# 03_iMX_8X_PMIC.net
KiCad netlist of a schematic drawn in Altium Designer
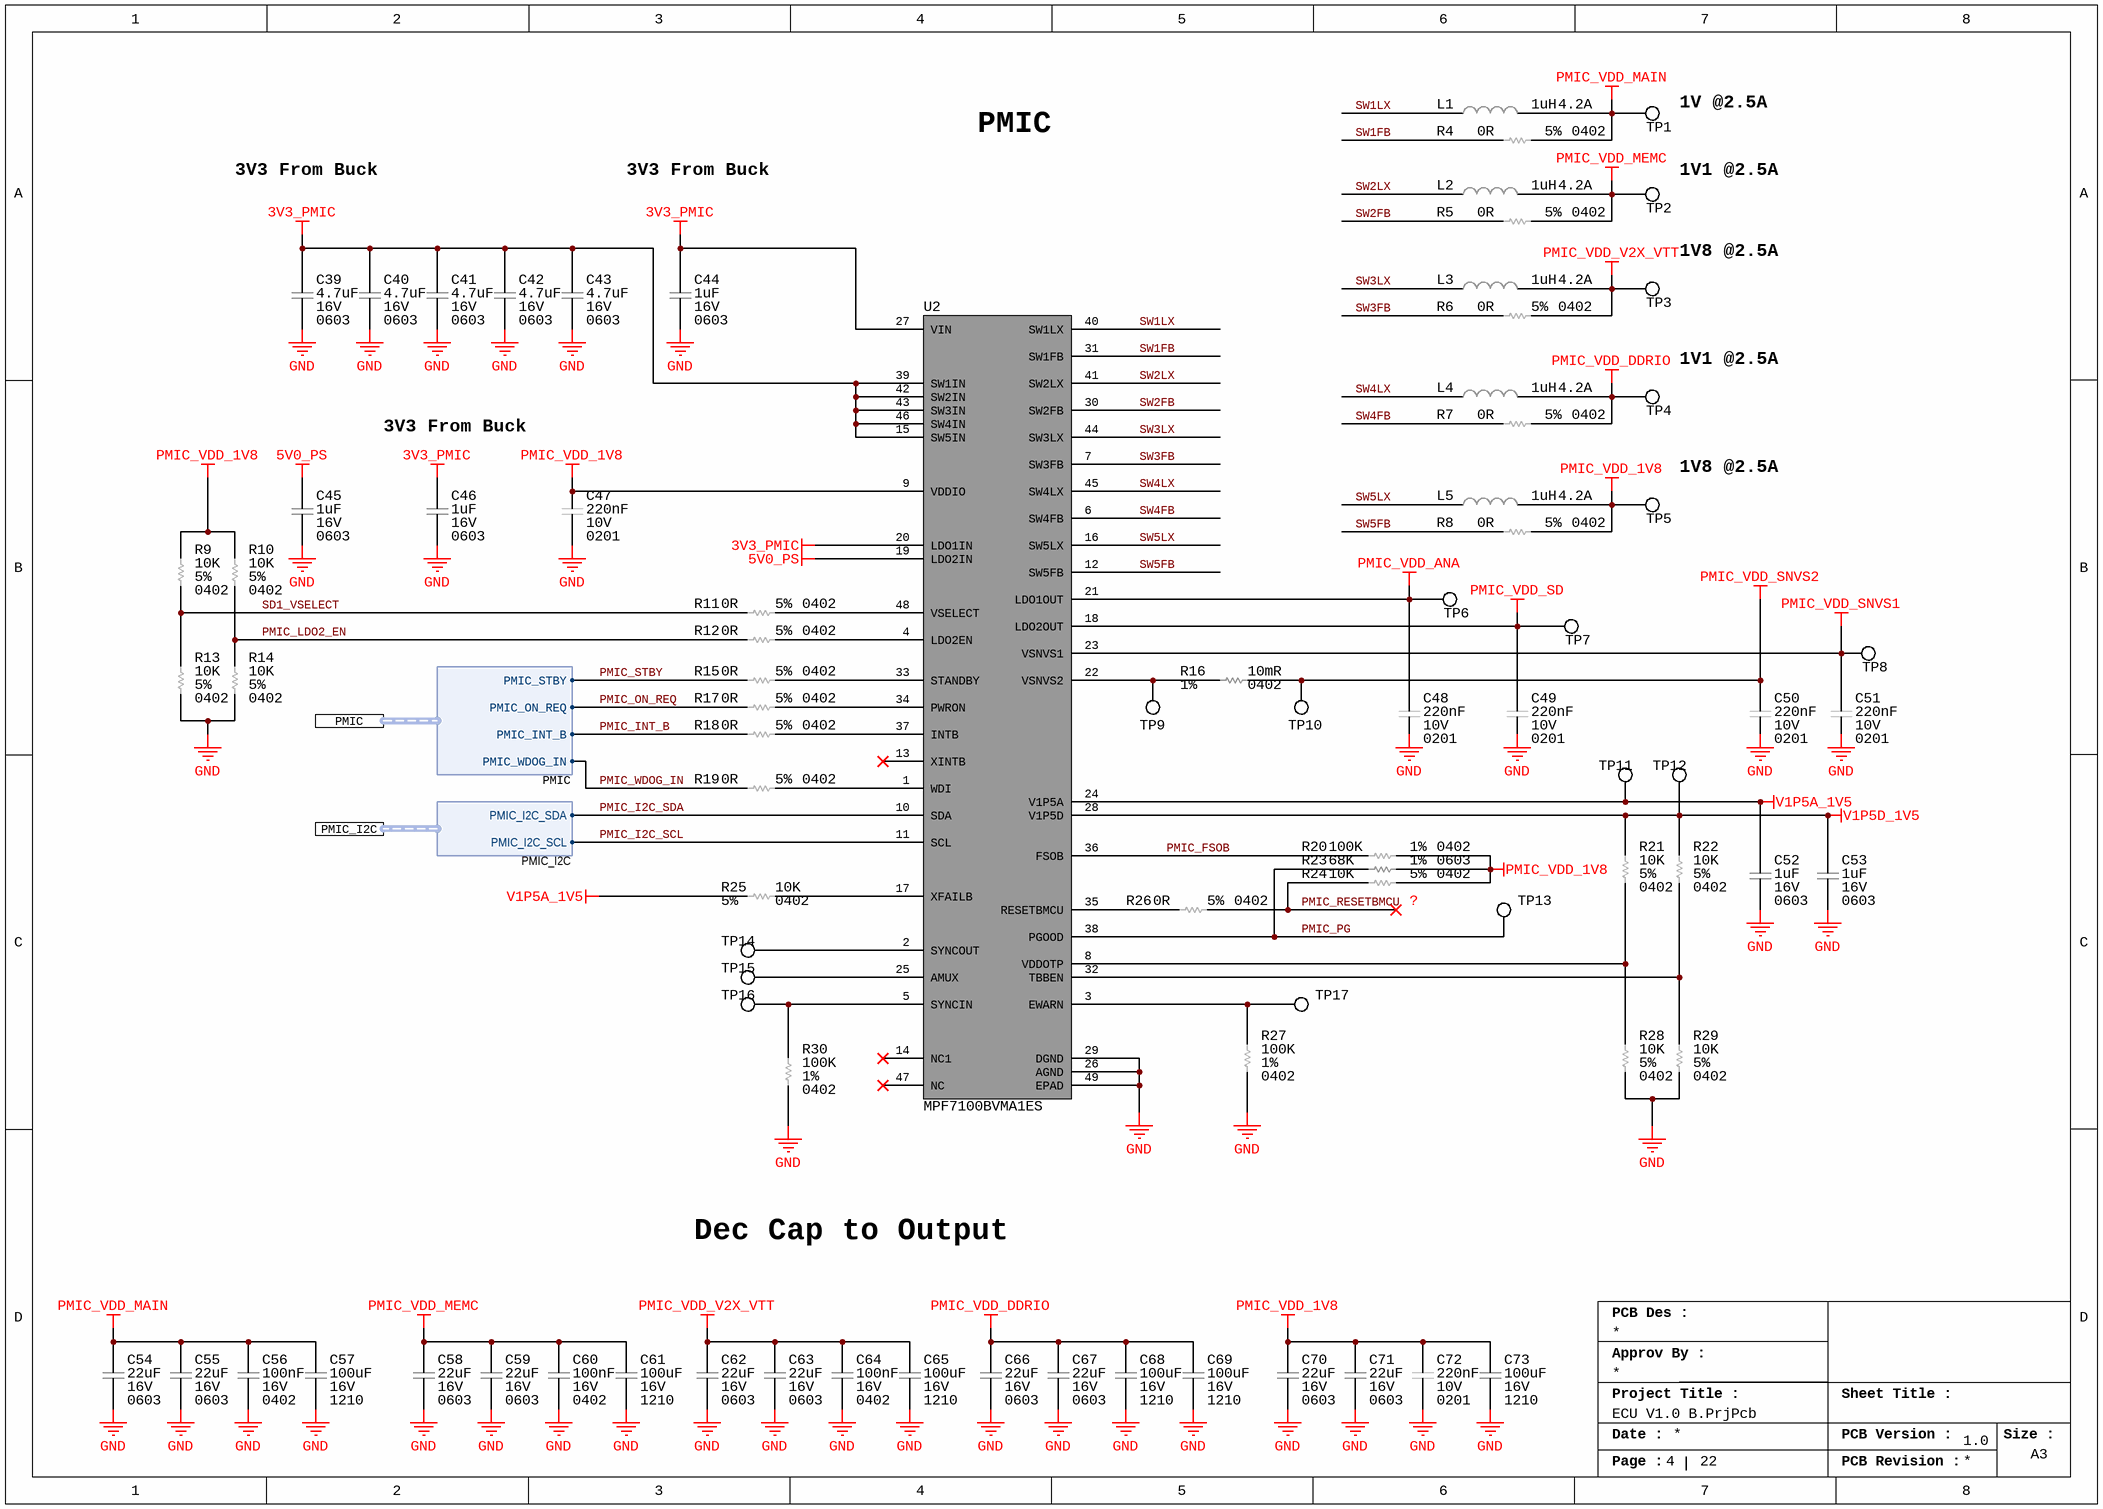
[diagram p0: 03_iMX 8X_PMIC.SchDoc]

(export (version "E")
  (design (tool "Eeschema 10.0.6"))
  (components
    (comp (ref "C39")
      (value "CL10A475KO8NNNC")
      (footprint "CAP_0603_CAPC1608X08N")
      (description "CAP CER 4.7UF 16V X5R 0603")
      (fields
        (field (name "MANUFACTURER") "Samsung")
        (field (name "TOLERANCE") "10%")
        (field (name "VOLTAGE") "16V")
        (field (name "CAPACITANCE") "4.7uF")
        (field (name "CASE/PACKAGE") "0603")
      )
      (libsource (lib "Electronic Devices_LIB") (part "CAP_4.7UF_16V_X5R_0603"))
    )
    (comp (ref "C40")
      (value "CL10A475KO8NNNC")
      (footprint "CAP_0603_CAPC1608X08N")
      (description "CAP CER 4.7UF 16V X5R 0603")
      (fields
        (field (name "MANUFACTURER") "Samsung")
        (field (name "TOLERANCE") "10%")
        (field (name "VOLTAGE") "16V")
        (field (name "CAPACITANCE") "4.7uF")
        (field (name "CASE/PACKAGE") "0603")
      )
      (libsource (lib "Electronic Devices_LIB") (part "CAP_4.7UF_16V_X5R_0603"))
    )
    (comp (ref "C41")
      (value "CL10A475KO8NNNC")
      (footprint "CAP_0603_CAPC1608X08N")
      (description "CAP CER 4.7UF 16V X5R 0603")
      (fields
        (field (name "MANUFACTURER") "Samsung")
        (field (name "TOLERANCE") "10%")
        (field (name "VOLTAGE") "16V")
        (field (name "CAPACITANCE") "4.7uF")
        (field (name "CASE/PACKAGE") "0603")
      )
      (libsource (lib "Electronic Devices_LIB") (part "CAP_4.7UF_16V_X5R_0603"))
    )
    (comp (ref "C42")
      (value "CL10A475KO8NNNC")
      (footprint "CAP_0603_CAPC1608X08N")
      (description "CAP CER 4.7UF 16V X5R 0603")
      (fields
        (field (name "MANUFACTURER") "Samsung")
        (field (name "TOLERANCE") "10%")
        (field (name "VOLTAGE") "16V")
        (field (name "CAPACITANCE") "4.7uF")
        (field (name "CASE/PACKAGE") "0603")
      )
      (libsource (lib "Electronic Devices_LIB") (part "CAP_4.7UF_16V_X5R_0603"))
    )
    (comp (ref "C43")
      (value "CL10A475KO8NNNC")
      (footprint "CAP_0603_CAPC1608X08N")
      (description "CAP CER 4.7UF 16V X5R 0603")
      (fields
        (field (name "MANUFACTURER") "Samsung")
        (field (name "TOLERANCE") "10%")
        (field (name "VOLTAGE") "16V")
        (field (name "CAPACITANCE") "4.7uF")
        (field (name "CASE/PACKAGE") "0603")
      )
      (libsource (lib "Electronic Devices_LIB") (part "CAP_4.7UF_16V_X5R_0603"))
    )
    (comp (ref "C44")
      (value "CL10A105KO8NNNC")
      (footprint "CAP_0603_CAPC1608X08N")
      (description "CAP CER 1UF 16V X5R 0603")
      (fields
        (field (name "MANUFACTURER") "Samsung")
        (field (name "TOLERANCE") "10%")
        (field (name "VOLTAGE RATING") "16V")
        (field (name "CAPACITANCE") "1uF")
        (field (name "CASE/PACKAGE") "0603")
      )
      (libsource (lib "Electronic Devices_LIB") (part "CAP_1UF_16V_X5R_0603"))
    )
    (comp (ref "C45")
      (value "CL10A105KO8NNNC")
      (footprint "CAP_0603_CAPC1608X08N")
      (description "CAP CER 1UF 16V X5R 0603")
      (fields
        (field (name "MANUFACTURER") "Samsung")
        (field (name "TOLERANCE") "10%")
        (field (name "VOLTAGE RATING") "16V")
        (field (name "CAPACITANCE") "1uF")
        (field (name "CASE/PACKAGE") "0603")
      )
      (libsource (lib "Electronic Devices_LIB") (part "CAP_1UF_16V_X5R_0603"))
    )
    (comp (ref "C46")
      (value "CL10A105KO8NNNC")
      (footprint "CAP_0603_CAPC1608X08N")
      (description "CAP CER 1UF 16V X5R 0603")
      (fields
        (field (name "MANUFACTURER") "Samsung")
        (field (name "TOLERANCE") "10%")
        (field (name "VOLTAGE RATING") "16V")
        (field (name "CAPACITANCE") "1uF")
        (field (name "CASE/PACKAGE") "0603")
      )
      (libsource (lib "Electronic Devices_LIB") (part "CAP_1UF_16V_X5R_0603"))
    )
    (comp (ref "C47")
      (value "LMK063BJ224MP-F")
      (footprint "CAP_0201_CAPC0603X03N")
      (description "Multilayer Ceramic Capacitors (High dielectric type), 10V, 0.22 uF, ± 20 %, 0201, X5R, RoHS")
      (fields
        (field (name "MANUFACTURER") "Taiyo Yuden")
        (field (name "TOLERANCE") "20%")
        (field (name "VOLTAGE RATING (DC)") "10V")
        (field (name "CAPACITANCE") "220nF")
        (field (name "CASE/PACKAGE") "0201")
      )
      (libsource (lib "Electronic Devices_LIB") (part "CAP_0.22UF_10V_X5R_0201"))
    )
    (comp (ref "C48")
      (value "LMK063BJ224MP-F")
      (footprint "CAP_0201_CAPC0603X03N")
      (description "Multilayer Ceramic Capacitors (High dielectric type), 10V, 0.22 uF, ± 20 %, 0201, X5R, RoHS")
      (fields
        (field (name "MANUFACTURER") "Taiyo Yuden")
        (field (name "TOLERANCE") "20%")
        (field (name "VOLTAGE RATING (DC)") "10V")
        (field (name "CAPACITANCE") "220nF")
        (field (name "CASE/PACKAGE") "0201")
      )
      (libsource (lib "Electronic Devices_LIB") (part "CAP_0.22UF_10V_X5R_0201"))
    )
    (comp (ref "C49")
      (value "LMK063BJ224MP-F")
      (footprint "CAP_0201_CAPC0603X03N")
      (description "Multilayer Ceramic Capacitors (High dielectric type), 10V, 0.22 uF, ± 20 %, 0201, X5R, RoHS")
      (fields
        (field (name "MANUFACTURER") "Taiyo Yuden")
        (field (name "TOLERANCE") "20%")
        (field (name "VOLTAGE RATING (DC)") "10V")
        (field (name "CAPACITANCE") "220nF")
        (field (name "CASE/PACKAGE") "0201")
      )
      (libsource (lib "Electronic Devices_LIB") (part "CAP_0.22UF_10V_X5R_0201"))
    )
    (comp (ref "C50")
      (value "LMK063BJ224MP-F")
      (footprint "CAP_0201_CAPC0603X03N")
      (description "Multilayer Ceramic Capacitors (High dielectric type), 10V, 0.22 uF, ± 20 %, 0201, X5R, RoHS")
      (fields
        (field (name "MANUFACTURER") "Taiyo Yuden")
        (field (name "TOLERANCE") "20%")
        (field (name "VOLTAGE RATING (DC)") "10V")
        (field (name "CAPACITANCE") "220nF")
        (field (name "CASE/PACKAGE") "0201")
      )
      (libsource (lib "Electronic Devices_LIB") (part "CAP_0.22UF_10V_X5R_0201"))
    )
    (comp (ref "C51")
      (value "LMK063BJ224MP-F")
      (footprint "CAP_0201_CAPC0603X03N")
      (description "Multilayer Ceramic Capacitors (High dielectric type), 10V, 0.22 uF, ± 20 %, 0201, X5R, RoHS")
      (fields
        (field (name "MANUFACTURER") "Taiyo Yuden")
        (field (name "TOLERANCE") "20%")
        (field (name "VOLTAGE RATING (DC)") "10V")
        (field (name "CAPACITANCE") "220nF")
        (field (name "CASE/PACKAGE") "0201")
      )
      (libsource (lib "Electronic Devices_LIB") (part "CAP_0.22UF_10V_X5R_0201"))
    )
    (comp (ref "C52")
      (value "CL10A105KO8NNNC")
      (footprint "CAP_0603_CAPC1608X08N")
      (description "CAP CER 1UF 16V X5R 0603")
      (fields
        (field (name "MANUFACTURER") "Samsung")
        (field (name "TOLERANCE") "10%")
        (field (name "VOLTAGE RATING") "16V")
        (field (name "CAPACITANCE") "1uF")
        (field (name "CASE/PACKAGE") "0603")
      )
      (libsource (lib "Electronic Devices_LIB") (part "CAP_1UF_16V_X5R_0603"))
    )
    (comp (ref "C53")
      (value "CL10A105KO8NNNC")
      (footprint "CAP_0603_CAPC1608X08N")
      (description "CAP CER 1UF 16V X5R 0603")
      (fields
        (field (name "MANUFACTURER") "Samsung")
        (field (name "TOLERANCE") "10%")
        (field (name "VOLTAGE RATING") "16V")
        (field (name "CAPACITANCE") "1uF")
        (field (name "CASE/PACKAGE") "0603")
      )
      (libsource (lib "Electronic Devices_LIB") (part "CAP_1UF_16V_X5R_0603"))
    )
    (comp (ref "C54")
      (value "CL10A226MO7JZNC")
      (footprint "CAP_0603_CAPC1608X08N")
      (description "Cap Ceramic 22uF 16V X5R 20% Pad SMD 0603 85C T/R")
      (fields
        (field (name "MANUFACTURER") "Samsung")
        (field (name "TOLERANCE") "20%")
        (field (name "CAPACITANCE") "22uF")
        (field (name "VOLTAGE RATING") "16V")
        (field (name "CASE/PACKAGE") "0603")
      )
      (libsource (lib "Electronic Devices_LIB") (part "CAP_22UF_16V_X5R_0603"))
    )
    (comp (ref "C55")
      (value "CL10A226MO7JZNC")
      (footprint "CAP_0603_CAPC1608X08N")
      (description "Cap Ceramic 22uF 16V X5R 20% Pad SMD 0603 85C T/R")
      (fields
        (field (name "MANUFACTURER") "Samsung")
        (field (name "TOLERANCE") "20%")
        (field (name "CAPACITANCE") "22uF")
        (field (name "VOLTAGE RATING") "16V")
        (field (name "CASE/PACKAGE") "0603")
      )
      (libsource (lib "Electronic Devices_LIB") (part "CAP_22UF_16V_X5R_0603"))
    )
    (comp (ref "C56")
      (value "CL05B104KO5NNNC")
      (footprint "CAP_0402_CAPC1005X05N")
      (description "Multilayer Ceramic Capacitor, 0.1 uF, 16 V, ± 10%, X7R, 0402 [1005 Metric]")
      (fields
        (field (name "MANUFACTURER") "Samsung")
        (field (name "TOLERANCE") "10%")
        (field (name "VOLTAGE RATING") "16V")
        (field (name "CAPACITANCE") "100nF")
        (field (name "CASE/PACKAGE") "0402")
      )
      (libsource (lib "Electronic Devices_LIB") (part "CAP_100NF_16V_X7R_0402"))
    )
    (comp (ref "C57")
      (value "EMK325ABJ107MM-T")
      (footprint "CAP_1210_CAPC3225X270N")
      (description "Multilayer Ceramic Capacitor, 100 uF, 16 V, ± 20%, X5R, 1210 [3225 Metric]")
      (fields
        (field (name "MANUFACTURER") "Taiyo Yuden")
        (field (name "TOLERANCE") "20%")
        (field (name "VOLTAGE RATING") "16V")
        (field (name "CAPACITANCE") "100uF")
        (field (name "CASE/PACKAGE") "1210")
      )
      (libsource (lib "Electronic Devices_LIB") (part "CAP_100UF_16V_X5R_1210"))
    )
    (comp (ref "C58")
      (value "CL10A226MO7JZNC")
      (footprint "CAP_0603_CAPC1608X08N")
      (description "Cap Ceramic 22uF 16V X5R 20% Pad SMD 0603 85C T/R")
      (fields
        (field (name "MANUFACTURER") "Samsung")
        (field (name "TOLERANCE") "20%")
        (field (name "CAPACITANCE") "22uF")
        (field (name "VOLTAGE RATING") "16V")
        (field (name "CASE/PACKAGE") "0603")
      )
      (libsource (lib "Electronic Devices_LIB") (part "CAP_22UF_16V_X5R_0603"))
    )
    (comp (ref "C59")
      (value "CL10A226MO7JZNC")
      (footprint "CAP_0603_CAPC1608X08N")
      (description "Cap Ceramic 22uF 16V X5R 20% Pad SMD 0603 85C T/R")
      (fields
        (field (name "MANUFACTURER") "Samsung")
        (field (name "TOLERANCE") "20%")
        (field (name "CAPACITANCE") "22uF")
        (field (name "VOLTAGE RATING") "16V")
        (field (name "CASE/PACKAGE") "0603")
      )
      (libsource (lib "Electronic Devices_LIB") (part "CAP_22UF_16V_X5R_0603"))
    )
    (comp (ref "C60")
      (value "CL05B104KO5NNNC")
      (footprint "CAP_0402_CAPC1005X05N")
      (description "Multilayer Ceramic Capacitor, 0.1 uF, 16 V, ± 10%, X7R, 0402 [1005 Metric]")
      (fields
        (field (name "MANUFACTURER") "Samsung")
        (field (name "TOLERANCE") "10%")
        (field (name "VOLTAGE RATING") "16V")
        (field (name "CAPACITANCE") "100nF")
        (field (name "CASE/PACKAGE") "0402")
      )
      (libsource (lib "Electronic Devices_LIB") (part "CAP_100NF_16V_X7R_0402"))
    )
    (comp (ref "C61")
      (value "EMK325ABJ107MM-T")
      (footprint "CAP_1210_CAPC3225X270N")
      (description "Multilayer Ceramic Capacitor, 100 uF, 16 V, ± 20%, X5R, 1210 [3225 Metric]")
      (fields
        (field (name "MANUFACTURER") "Taiyo Yuden")
        (field (name "TOLERANCE") "20%")
        (field (name "VOLTAGE RATING") "16V")
        (field (name "CAPACITANCE") "100uF")
        (field (name "CASE/PACKAGE") "1210")
      )
      (libsource (lib "Electronic Devices_LIB") (part "CAP_100UF_16V_X5R_1210"))
    )
    (comp (ref "C62")
      (value "CL10A226MO7JZNC")
      (footprint "CAP_0603_CAPC1608X08N")
      (description "Cap Ceramic 22uF 16V X5R 20% Pad SMD 0603 85C T/R")
      (fields
        (field (name "MANUFACTURER") "Samsung")
        (field (name "TOLERANCE") "20%")
        (field (name "CAPACITANCE") "22uF")
        (field (name "VOLTAGE RATING") "16V")
        (field (name "CASE/PACKAGE") "0603")
      )
      (libsource (lib "Electronic Devices_LIB") (part "CAP_22UF_16V_X5R_0603"))
    )
    (comp (ref "C63")
      (value "CL10A226MO7JZNC")
      (footprint "CAP_0603_CAPC1608X08N")
      (description "Cap Ceramic 22uF 16V X5R 20% Pad SMD 0603 85C T/R")
      (fields
        (field (name "MANUFACTURER") "Samsung")
        (field (name "TOLERANCE") "20%")
        (field (name "CAPACITANCE") "22uF")
        (field (name "VOLTAGE RATING") "16V")
        (field (name "CASE/PACKAGE") "0603")
      )
      (libsource (lib "Electronic Devices_LIB") (part "CAP_22UF_16V_X5R_0603"))
    )
    (comp (ref "C64")
      (value "CL05B104KO5NNNC")
      (footprint "CAP_0402_CAPC1005X05N")
      (description "Multilayer Ceramic Capacitor, 0.1 uF, 16 V, ± 10%, X7R, 0402 [1005 Metric]")
      (fields
        (field (name "MANUFACTURER") "Samsung")
        (field (name "TOLERANCE") "10%")
        (field (name "VOLTAGE RATING") "16V")
        (field (name "CAPACITANCE") "100nF")
        (field (name "CASE/PACKAGE") "0402")
      )
      (libsource (lib "Electronic Devices_LIB") (part "CAP_100NF_16V_X7R_0402"))
    )
    (comp (ref "C65")
      (value "EMK325ABJ107MM-T")
      (footprint "CAP_1210_CAPC3225X270N")
      (description "Multilayer Ceramic Capacitor, 100 uF, 16 V, ± 20%, X5R, 1210 [3225 Metric]")
      (fields
        (field (name "MANUFACTURER") "Taiyo Yuden")
        (field (name "TOLERANCE") "20%")
        (field (name "VOLTAGE RATING") "16V")
        (field (name "CAPACITANCE") "100uF")
        (field (name "CASE/PACKAGE") "1210")
      )
      (libsource (lib "Electronic Devices_LIB") (part "CAP_100UF_16V_X5R_1210"))
    )
    (comp (ref "C66")
      (value "CL10A226MO7JZNC")
      (footprint "CAP_0603_CAPC1608X08N")
      (description "Cap Ceramic 22uF 16V X5R 20% Pad SMD 0603 85C T/R")
      (fields
        (field (name "MANUFACTURER") "Samsung")
        (field (name "TOLERANCE") "20%")
        (field (name "CAPACITANCE") "22uF")
        (field (name "VOLTAGE RATING") "16V")
        (field (name "CASE/PACKAGE") "0603")
      )
      (libsource (lib "Electronic Devices_LIB") (part "CAP_22UF_16V_X5R_0603"))
    )
    (comp (ref "C67")
      (value "CL10A226MO7JZNC")
      (footprint "CAP_0603_CAPC1608X08N")
      (description "Cap Ceramic 22uF 16V X5R 20% Pad SMD 0603 85C T/R")
      (fields
        (field (name "MANUFACTURER") "Samsung")
        (field (name "TOLERANCE") "20%")
        (field (name "CAPACITANCE") "22uF")
        (field (name "VOLTAGE RATING") "16V")
        (field (name "CASE/PACKAGE") "0603")
      )
      (libsource (lib "Electronic Devices_LIB") (part "CAP_22UF_16V_X5R_0603"))
    )
    (comp (ref "C68")
      (value "EMK325ABJ107MM-T")
      (footprint "CAP_1210_CAPC3225X270N")
      (description "Multilayer Ceramic Capacitor, 100 uF, 16 V, ± 20%, X5R, 1210 [3225 Metric]")
      (fields
        (field (name "MANUFACTURER") "Taiyo Yuden")
        (field (name "TOLERANCE") "20%")
        (field (name "VOLTAGE RATING") "16V")
        (field (name "CAPACITANCE") "100uF")
        (field (name "CASE/PACKAGE") "1210")
      )
      (libsource (lib "Electronic Devices_LIB") (part "CAP_100UF_16V_X5R_1210"))
    )
    (comp (ref "C69")
      (value "EMK325ABJ107MM-T")
      (footprint "CAP_1210_CAPC3225X270N")
      (description "Multilayer Ceramic Capacitor, 100 uF, 16 V, ± 20%, X5R, 1210 [3225 Metric]")
      (fields
        (field (name "MANUFACTURER") "Taiyo Yuden")
        (field (name "TOLERANCE") "20%")
        (field (name "VOLTAGE RATING") "16V")
        (field (name "CAPACITANCE") "100uF")
        (field (name "CASE/PACKAGE") "1210")
      )
      (libsource (lib "Electronic Devices_LIB") (part "CAP_100UF_16V_X5R_1210"))
    )
    (comp (ref "C70")
      (value "CL10A226MO7JZNC")
      (footprint "CAP_0603_CAPC1608X08N")
      (description "Cap Ceramic 22uF 16V X5R 20% Pad SMD 0603 85C T/R")
      (fields
        (field (name "MANUFACTURER") "Samsung")
        (field (name "TOLERANCE") "20%")
        (field (name "CAPACITANCE") "22uF")
        (field (name "VOLTAGE RATING") "16V")
        (field (name "CASE/PACKAGE") "0603")
      )
      (libsource (lib "Electronic Devices_LIB") (part "CAP_22UF_16V_X5R_0603"))
    )
    (comp (ref "C71")
      (value "CL10A226MO7JZNC")
      (footprint "CAP_0603_CAPC1608X08N")
      (description "Cap Ceramic 22uF 16V X5R 20% Pad SMD 0603 85C T/R")
      (fields
        (field (name "MANUFACTURER") "Samsung")
        (field (name "TOLERANCE") "20%")
        (field (name "CAPACITANCE") "22uF")
        (field (name "VOLTAGE RATING") "16V")
        (field (name "CASE/PACKAGE") "0603")
      )
      (libsource (lib "Electronic Devices_LIB") (part "CAP_22UF_16V_X5R_0603"))
    )
    (comp (ref "C72")
      (value "LMK063BJ224MP-F")
      (footprint "CAP_0201_CAPC0603X03N")
      (description "Multilayer Ceramic Capacitors (High dielectric type), 10V, 0.22 uF, ± 20 %, 0201, X5R, RoHS")
      (fields
        (field (name "MANUFACTURER") "Taiyo Yuden")
        (field (name "TOLERANCE") "20%")
        (field (name "VOLTAGE RATING (DC)") "10V")
        (field (name "CAPACITANCE") "220nF")
        (field (name "CASE/PACKAGE") "0201")
      )
      (libsource (lib "Electronic Devices_LIB") (part "CAP_0.22UF_10V_X5R_0201"))
    )
    (comp (ref "C73")
      (value "EMK325ABJ107MM-T")
      (footprint "CAP_1210_CAPC3225X270N")
      (description "Multilayer Ceramic Capacitor, 100 uF, 16 V, ± 20%, X5R, 1210 [3225 Metric]")
      (fields
        (field (name "MANUFACTURER") "Taiyo Yuden")
        (field (name "TOLERANCE") "20%")
        (field (name "VOLTAGE RATING") "16V")
        (field (name "CAPACITANCE") "100uF")
        (field (name "CASE/PACKAGE") "1210")
      )
      (libsource (lib "Electronic Devices_LIB") (part "CAP_100UF_16V_X5R_1210"))
    )
    (comp (ref "L1")
      (value "TFM252012ALMA1R0MTAA")
      (footprint "INDC2520X120N")
      (description "Inductor Power Shielded Thin Film 1uH 20% 1MHz Metal 3.7A 0.042Ohm DCR 1008 Automotive T/R")
      (fields
        (field (name "MANUFACTURER") "TDK")
        (field (name "TOLERANCE") "20%")
        (field (name "SATURATION CURRENT") "4.2A")
        (field (name "INDUCTANCE") "1uH")
      )
      (libsource (lib "Electronic Devices_LIB") (part "IND_1uH_3.7A_TFM252012ALMA1R0MTAA"))
    )
    (comp (ref "L2")
      (value "TFM252012ALMA1R0MTAA")
      (footprint "INDC2520X120N")
      (description "Inductor Power Shielded Thin Film 1uH 20% 1MHz Metal 3.7A 0.042Ohm DCR 1008 Automotive T/R")
      (fields
        (field (name "MANUFACTURER") "TDK")
        (field (name "TOLERANCE") "20%")
        (field (name "SATURATION CURRENT") "4.2A")
        (field (name "INDUCTANCE") "1uH")
      )
      (libsource (lib "Electronic Devices_LIB") (part "IND_1uH_3.7A_TFM252012ALMA1R0MTAA"))
    )
    (comp (ref "L3")
      (value "TFM252012ALMA1R0MTAA")
      (footprint "INDC2520X120N")
      (description "Inductor Power Shielded Thin Film 1uH 20% 1MHz Metal 3.7A 0.042Ohm DCR 1008 Automotive T/R")
      (fields
        (field (name "MANUFACTURER") "TDK")
        (field (name "TOLERANCE") "20%")
        (field (name "SATURATION CURRENT") "4.2A")
        (field (name "INDUCTANCE") "1uH")
      )
      (libsource (lib "Electronic Devices_LIB") (part "IND_1uH_3.7A_TFM252012ALMA1R0MTAA"))
    )
    (comp (ref "L4")
      (value "TFM252012ALMA1R0MTAA")
      (footprint "INDC2520X120N")
      (description "Inductor Power Shielded Thin Film 1uH 20% 1MHz Metal 3.7A 0.042Ohm DCR 1008 Automotive T/R")
      (fields
        (field (name "MANUFACTURER") "TDK")
        (field (name "TOLERANCE") "20%")
        (field (name "SATURATION CURRENT") "4.2A")
        (field (name "INDUCTANCE") "1uH")
      )
      (libsource (lib "Electronic Devices_LIB") (part "IND_1uH_3.7A_TFM252012ALMA1R0MTAA"))
    )
    (comp (ref "L5")
      (value "TFM252012ALMA1R0MTAA")
      (footprint "INDC2520X120N")
      (description "Inductor Power Shielded Thin Film 1uH 20% 1MHz Metal 3.7A 0.042Ohm DCR 1008 Automotive T/R")
      (fields
        (field (name "MANUFACTURER") "TDK")
        (field (name "TOLERANCE") "20%")
        (field (name "SATURATION CURRENT") "4.2A")
        (field (name "INDUCTANCE") "1uH")
      )
      (libsource (lib "Electronic Devices_LIB") (part "IND_1uH_3.7A_TFM252012ALMA1R0MTAA"))
    )
    (comp (ref "R4")
      (value "ERJ-2GE0R00X")
      (footprint "RES_0402_RESC1005X04N")
      (description "SMD Chip Resistor, Jumper, 0 ohm, 100 mW, 0402 [1005 Metric], Thick Film, General Purpose")
      (fields
        (field (name "MANUFACTURER") "Panasonic")
        (field (name "CASE CODE (IMPERIAL)") "0402")
        (field (name "TOLERANCE") "5%")
        (field (name "RESISTANCE") "0R")
      )
      (libsource (lib "Electronic Devices_LIB") (part "RES_0R_5%_100mW_0402"))
    )
    (comp (ref "R5")
      (value "ERJ-2GE0R00X")
      (footprint "RES_0402_RESC1005X04N")
      (description "SMD Chip Resistor, Jumper, 0 ohm, 100 mW, 0402 [1005 Metric], Thick Film, General Purpose")
      (fields
        (field (name "MANUFACTURER") "Panasonic")
        (field (name "CASE CODE (IMPERIAL)") "0402")
        (field (name "TOLERANCE") "5%")
        (field (name "RESISTANCE") "0R")
      )
      (libsource (lib "Electronic Devices_LIB") (part "RES_0R_5%_100mW_0402"))
    )
    (comp (ref "R6")
      (value "ERJ-2GE0R00X")
      (footprint "RES_0402_RESC1005X04N")
      (description "SMD Chip Resistor, Jumper, 0 ohm, 100 mW, 0402 [1005 Metric], Thick Film, General Purpose")
      (fields
        (field (name "MANUFACTURER") "Panasonic")
        (field (name "CASE CODE (IMPERIAL)") "0402")
        (field (name "TOLERANCE") "5%")
        (field (name "RESISTANCE") "0R")
      )
      (libsource (lib "Electronic Devices_LIB") (part "RES_0R_5%_100mW_0402"))
    )
    (comp (ref "R7")
      (value "ERJ-2GE0R00X")
      (footprint "RES_0402_RESC1005X04N")
      (description "SMD Chip Resistor, Jumper, 0 ohm, 100 mW, 0402 [1005 Metric], Thick Film, General Purpose")
      (fields
        (field (name "MANUFACTURER") "Panasonic")
        (field (name "CASE CODE (IMPERIAL)") "0402")
        (field (name "TOLERANCE") "5%")
        (field (name "RESISTANCE") "0R")
      )
      (libsource (lib "Electronic Devices_LIB") (part "RES_0R_5%_100mW_0402"))
    )
    (comp (ref "R8")
      (value "ERJ-2GE0R00X")
      (footprint "RES_0402_RESC1005X04N")
      (description "SMD Chip Resistor, Jumper, 0 ohm, 100 mW, 0402 [1005 Metric], Thick Film, General Purpose")
      (fields
        (field (name "MANUFACTURER") "Panasonic")
        (field (name "CASE CODE (IMPERIAL)") "0402")
        (field (name "TOLERANCE") "5%")
        (field (name "RESISTANCE") "0R")
      )
      (libsource (lib "Electronic Devices_LIB") (part "RES_0R_5%_100mW_0402"))
    )
    (comp (ref "R9")
      (value "ERJ-2GEJ103X")
      (footprint "RES_0402_RESC1005X04N")
      (description "Res Thick Film 0402 10K Ohm 5% 1/10W ±200ppm/°C Molded SMD Punched Carrier T/R")
      (fields
        (field (name "MANUFACTURER") "Panasonic")
        (field (name "TOLERANCE") "5%")
        (field (name "RESISTANCE") "10K")
        (field (name "CASE/PACKAGE") "0402")
      )
      (libsource (lib "Electronic Devices_LIB") (part "RES_10K_5%_100mW_0402"))
    )
    (comp (ref "R10")
      (value "ERJ-2GEJ103X")
      (footprint "RES_0402_RESC1005X04N")
      (description "Res Thick Film 0402 10K Ohm 5% 1/10W ±200ppm/°C Molded SMD Punched Carrier T/R")
      (fields
        (field (name "MANUFACTURER") "Panasonic")
        (field (name "TOLERANCE") "5%")
        (field (name "RESISTANCE") "10K")
        (field (name "CASE/PACKAGE") "0402")
      )
      (libsource (lib "Electronic Devices_LIB") (part "RES_10K_5%_100mW_0402"))
    )
    (comp (ref "R11")
      (value "ERJ-2GE0R00X")
      (footprint "RES_0402_RESC1005X04N")
      (description "SMD Chip Resistor, Jumper, 0 ohm, 100 mW, 0402 [1005 Metric], Thick Film, General Purpose")
      (fields
        (field (name "MANUFACTURER") "Panasonic")
        (field (name "CASE CODE (IMPERIAL)") "0402")
        (field (name "TOLERANCE") "5%")
        (field (name "RESISTANCE") "0R")
      )
      (libsource (lib "Electronic Devices_LIB") (part "RES_0R_5%_100mW_0402"))
    )
    (comp (ref "R12")
      (value "ERJ-2GE0R00X")
      (footprint "RES_0402_RESC1005X04N")
      (description "SMD Chip Resistor, Jumper, 0 ohm, 100 mW, 0402 [1005 Metric], Thick Film, General Purpose")
      (fields
        (field (name "MANUFACTURER") "Panasonic")
        (field (name "CASE CODE (IMPERIAL)") "0402")
        (field (name "TOLERANCE") "5%")
        (field (name "RESISTANCE") "0R")
      )
      (libsource (lib "Electronic Devices_LIB") (part "RES_0R_5%_100mW_0402"))
    )
    (comp (ref "R13")
      (value "ERJ-2GEJ103X")
      (footprint "RES_0402_RESC1005X04N")
      (description "Res Thick Film 0402 10K Ohm 5% 1/10W ±200ppm/°C Molded SMD Punched Carrier T/R")
      (fields
        (field (name "MANUFACTURER") "Panasonic")
        (field (name "TOLERANCE") "5%")
        (field (name "RESISTANCE") "10K")
        (field (name "CASE/PACKAGE") "0402")
      )
      (libsource (lib "Electronic Devices_LIB") (part "RES_10K_5%_100mW_0402"))
    )
    (comp (ref "R14")
      (value "ERJ-2GEJ103X")
      (footprint "RES_0402_RESC1005X04N")
      (description "Res Thick Film 0402 10K Ohm 5% 1/10W ±200ppm/°C Molded SMD Punched Carrier T/R")
      (fields
        (field (name "MANUFACTURER") "Panasonic")
        (field (name "TOLERANCE") "5%")
        (field (name "RESISTANCE") "10K")
        (field (name "CASE/PACKAGE") "0402")
      )
      (libsource (lib "Electronic Devices_LIB") (part "RES_10K_5%_100mW_0402"))
    )
    (comp (ref "R15")
      (value "ERJ-2GE0R00X")
      (footprint "RES_0402_RESC1005X04N")
      (description "SMD Chip Resistor, Jumper, 0 ohm, 100 mW, 0402 [1005 Metric], Thick Film, General Purpose")
      (fields
        (field (name "MANUFACTURER") "Panasonic")
        (field (name "CASE CODE (IMPERIAL)") "0402")
        (field (name "TOLERANCE") "5%")
        (field (name "RESISTANCE") "0R")
      )
      (libsource (lib "Electronic Devices_LIB") (part "RES_0R_5%_100mW_0402"))
    )
    (comp (ref "R16")
      (value "ERJ-2LWFR010X")
      (footprint "RES_0603_RESC1608X04N")
      (description "Res Current Sense Thick Film 0402 0.01 Ohm 1% 1/5W 0ppm/°C to 500ppm/°C Molded T/R")
      (fields
        (field (name "MANUFACTURER") "Panasonic")
        (field (name "TOLERANCE") "1%")
        (field (name "RESISTANCE") "10mR")
        (field (name "CASE/PACKAGE") "0402")
      )
      (libsource (lib "Electronic Devices_LIB") (part "RES_10mR_1%_0.05W_0402"))
    )
    (comp (ref "R17")
      (value "ERJ-2GE0R00X")
      (footprint "RES_0402_RESC1005X04N")
      (description "SMD Chip Resistor, Jumper, 0 ohm, 100 mW, 0402 [1005 Metric], Thick Film, General Purpose")
      (fields
        (field (name "MANUFACTURER") "Panasonic")
        (field (name "CASE CODE (IMPERIAL)") "0402")
        (field (name "TOLERANCE") "5%")
        (field (name "RESISTANCE") "0R")
      )
      (libsource (lib "Electronic Devices_LIB") (part "RES_0R_5%_100mW_0402"))
    )
    (comp (ref "R18")
      (value "ERJ-2GE0R00X")
      (footprint "RES_0402_RESC1005X04N")
      (description "SMD Chip Resistor, Jumper, 0 ohm, 100 mW, 0402 [1005 Metric], Thick Film, General Purpose")
      (fields
        (field (name "MANUFACTURER") "Panasonic")
        (field (name "CASE CODE (IMPERIAL)") "0402")
        (field (name "TOLERANCE") "5%")
        (field (name "RESISTANCE") "0R")
      )
      (libsource (lib "Electronic Devices_LIB") (part "RES_0R_5%_100mW_0402"))
    )
    (comp (ref "R19")
      (value "ERJ-2GE0R00X")
      (footprint "RES_0402_RESC1005X04N")
      (description "SMD Chip Resistor, Jumper, 0 ohm, 100 mW, 0402 [1005 Metric], Thick Film, General Purpose")
      (fields
        (field (name "MANUFACTURER") "Panasonic")
        (field (name "CASE CODE (IMPERIAL)") "0402")
        (field (name "TOLERANCE") "5%")
        (field (name "RESISTANCE") "0R")
      )
      (libsource (lib "Electronic Devices_LIB") (part "RES_0R_5%_100mW_0402"))
    )
    (comp (ref "R20")
      (value "RC0402FR-07100KL")
      (footprint "RES_0402_RESC1005X04N")
      (description "SMD Chip Resistor, 100 kOhm, ± 1%, 63 mW, 0402 [1005 Metric], Thick Film, General Purpose")
      (fields
        (field (name "MANUFACTURER") "Yageo")
        (field (name "RESISTANCE") "100K")
        (field (name "TOLERANCE") "1%")
        (field (name "CASE/PACKAGE") "0402")
      )
      (libsource (lib "Electronic Devices_LIB") (part "RES_100K_1%_100mW_0402"))
    )
    (comp (ref "R21")
      (value "ERJ-2GEJ103X")
      (footprint "RES_0402_RESC1005X04N")
      (description "Res Thick Film 0402 10K Ohm 5% 1/10W ±200ppm/°C Molded SMD Punched Carrier T/R")
      (fields
        (field (name "MANUFACTURER") "Panasonic")
        (field (name "TOLERANCE") "5%")
        (field (name "RESISTANCE") "10K")
        (field (name "CASE/PACKAGE") "0402")
      )
      (libsource (lib "Electronic Devices_LIB") (part "RES_10K_5%_100mW_0402"))
    )
    (comp (ref "R22")
      (value "ERJ-2GEJ103X")
      (footprint "RES_0402_RESC1005X04N")
      (description "Res Thick Film 0402 10K Ohm 5% 1/10W ±200ppm/°C Molded SMD Punched Carrier T/R")
      (fields
        (field (name "MANUFACTURER") "Panasonic")
        (field (name "TOLERANCE") "5%")
        (field (name "RESISTANCE") "10K")
        (field (name "CASE/PACKAGE") "0402")
      )
      (libsource (lib "Electronic Devices_LIB") (part "RES_10K_5%_100mW_0402"))
    )
    (comp (ref "R23")
      (value "RC0603FR-0768KL")
      (footprint "RES_0603_RESC1608X04N")
      (description "SMD Chip Resistor, 68 kOhm, ± 1%, 100 mW, 0603 [1608 Metric], Thick Film, General Purpose")
      (fields
        (field (name "MANUFACTURER") "Yageo")
        (field (name "TOLERANCE") "1%")
        (field (name "RESISTANCE") "68K")
        (field (name "CASE/PACKAGE") "0603")
      )
      (libsource (lib "Electronic Devices_LIB") (part "RES_68K_1%_100mW_0603"))
    )
    (comp (ref "R24")
      (value "ERJ-2GEJ103X")
      (footprint "RES_0402_RESC1005X04N")
      (description "Res Thick Film 0402 10K Ohm 5% 1/10W ±200ppm/°C Molded SMD Punched Carrier T/R")
      (fields
        (field (name "MANUFACTURER") "Panasonic")
        (field (name "TOLERANCE") "5%")
        (field (name "RESISTANCE") "10K")
        (field (name "CASE/PACKAGE") "0402")
      )
      (libsource (lib "Electronic Devices_LIB") (part "RES_10K_5%_100mW_0402"))
    )
    (comp (ref "R25")
      (value "ERJ-2GEJ103X")
      (footprint "RES_0402_RESC1005X04N")
      (description "Res Thick Film 0402 10K Ohm 5% 1/10W ±200ppm/°C Molded SMD Punched Carrier T/R")
      (fields
        (field (name "MANUFACTURER") "Panasonic")
        (field (name "TOLERANCE") "5%")
        (field (name "RESISTANCE") "10K")
        (field (name "CASE/PACKAGE") "0402")
      )
      (libsource (lib "Electronic Devices_LIB") (part "RES_10K_5%_100mW_0402"))
    )
    (comp (ref "R26")
      (value "ERJ-2GE0R00X")
      (footprint "RES_0402_RESC1005X04N")
      (description "SMD Chip Resistor, Jumper, 0 ohm, 100 mW, 0402 [1005 Metric], Thick Film, General Purpose")
      (fields
        (field (name "MANUFACTURER") "Panasonic")
        (field (name "CASE CODE (IMPERIAL)") "0402")
        (field (name "TOLERANCE") "5%")
        (field (name "RESISTANCE") "0R")
      )
      (libsource (lib "Electronic Devices_LIB") (part "RES_0R_5%_100mW_0402"))
    )
    (comp (ref "R27")
      (value "RC0402FR-07100KL")
      (footprint "RES_0402_RESC1005X04N")
      (description "SMD Chip Resistor, 100 kOhm, ± 1%, 63 mW, 0402 [1005 Metric], Thick Film, General Purpose")
      (fields
        (field (name "MANUFACTURER") "Yageo")
        (field (name "RESISTANCE") "100K")
        (field (name "TOLERANCE") "1%")
        (field (name "CASE/PACKAGE") "0402")
      )
      (libsource (lib "Electronic Devices_LIB") (part "RES_100K_1%_100mW_0402"))
    )
    (comp (ref "R28")
      (value "ERJ-2GEJ103X")
      (footprint "RES_0402_RESC1005X04N")
      (description "Res Thick Film 0402 10K Ohm 5% 1/10W ±200ppm/°C Molded SMD Punched Carrier T/R")
      (fields
        (field (name "MANUFACTURER") "Panasonic")
        (field (name "TOLERANCE") "5%")
        (field (name "RESISTANCE") "10K")
        (field (name "CASE/PACKAGE") "0402")
      )
      (libsource (lib "Electronic Devices_LIB") (part "RES_10K_5%_100mW_0402"))
    )
    (comp (ref "R29")
      (value "ERJ-2GEJ103X")
      (footprint "RES_0402_RESC1005X04N")
      (description "Res Thick Film 0402 10K Ohm 5% 1/10W ±200ppm/°C Molded SMD Punched Carrier T/R")
      (fields
        (field (name "MANUFACTURER") "Panasonic")
        (field (name "TOLERANCE") "5%")
        (field (name "RESISTANCE") "10K")
        (field (name "CASE/PACKAGE") "0402")
      )
      (libsource (lib "Electronic Devices_LIB") (part "RES_10K_5%_100mW_0402"))
    )
    (comp (ref "R30")
      (value "RC0402FR-07100KL")
      (footprint "RES_0402_RESC1005X04N")
      (description "SMD Chip Resistor, 100 kOhm, ± 1%, 63 mW, 0402 [1005 Metric], Thick Film, General Purpose")
      (fields
        (field (name "MANUFACTURER") "Yageo")
        (field (name "RESISTANCE") "100K")
        (field (name "TOLERANCE") "1%")
        (field (name "CASE/PACKAGE") "0402")
      )
      (libsource (lib "Electronic Devices_LIB") (part "RES_100K_1%_100mW_0402"))
    )
    (comp (ref "TP1")
      (value "NO COMPONENT")
      (footprint "TP_PAD_0.5MM_SMD_ROUND")
      (description "Test Point, SMD pad, round, 1.5mm, 1.6mm, 3mm diameter")
      (libsource (lib "Electronic Devices_LIB") (part "TP_PAD_SMD_SMALL"))
    )
    (comp (ref "TP2")
      (value "NO COMPONENT")
      (footprint "TP_PAD_0.5MM_SMD_ROUND")
      (description "Test Point, SMD pad, round, 1.5mm, 1.6mm, 3mm diameter")
      (libsource (lib "Electronic Devices_LIB") (part "TP_PAD_SMD_SMALL"))
    )
    (comp (ref "TP3")
      (value "NO COMPONENT")
      (footprint "TP_PAD_0.5MM_SMD_ROUND")
      (description "Test Point, SMD pad, round, 1.5mm, 1.6mm, 3mm diameter")
      (libsource (lib "Electronic Devices_LIB") (part "TP_PAD_SMD_SMALL"))
    )
    (comp (ref "TP4")
      (value "NO COMPONENT")
      (footprint "TP_PAD_0.5MM_SMD_ROUND")
      (description "Test Point, SMD pad, round, 1.5mm, 1.6mm, 3mm diameter")
      (libsource (lib "Electronic Devices_LIB") (part "TP_PAD_SMD_SMALL"))
    )
    (comp (ref "TP5")
      (value "NO COMPONENT")
      (footprint "TP_PAD_0.5MM_SMD_ROUND")
      (description "Test Point, SMD pad, round, 1.5mm, 1.6mm, 3mm diameter")
      (libsource (lib "Electronic Devices_LIB") (part "TP_PAD_SMD_SMALL"))
    )
    (comp (ref "TP6")
      (value "NO COMPONENT")
      (footprint "TP_PAD_0.5MM_SMD_ROUND")
      (description "Test Point, SMD pad, round, 1.5mm, 1.6mm, 3mm diameter")
      (libsource (lib "Electronic Devices_LIB") (part "TP_PAD_SMD_SMALL"))
    )
    (comp (ref "TP7")
      (value "NO COMPONENT")
      (footprint "TP_PAD_0.5MM_SMD_ROUND")
      (description "Test Point, SMD pad, round, 1.5mm, 1.6mm, 3mm diameter")
      (libsource (lib "Electronic Devices_LIB") (part "TP_PAD_SMD_SMALL"))
    )
    (comp (ref "TP8")
      (value "NO COMPONENT")
      (footprint "TP_PAD_0.5MM_SMD_ROUND")
      (description "Test Point, SMD pad, round, 1.5mm, 1.6mm, 3mm diameter")
      (libsource (lib "Electronic Devices_LIB") (part "TP_PAD_SMD_SMALL"))
    )
    (comp (ref "TP9")
      (value "NO COMPONENT")
      (footprint "TP_PAD_0.5MM_SMD_ROUND")
      (description "Test Point, SMD pad, round, 1.5mm, 1.6mm, 3mm diameter")
      (libsource (lib "Electronic Devices_LIB") (part "TP_PAD_SMD_SMALL"))
    )
    (comp (ref "TP10")
      (value "NO COMPONENT")
      (footprint "TP_PAD_0.5MM_SMD_ROUND")
      (description "Test Point, SMD pad, round, 1.5mm, 1.6mm, 3mm diameter")
      (libsource (lib "Electronic Devices_LIB") (part "TP_PAD_SMD_SMALL"))
    )
    (comp (ref "TP11")
      (value "NO COMPONENT")
      (footprint "TP_PAD_0.5MM_SMD_ROUND")
      (description "Test Point, SMD pad, round, 1.5mm, 1.6mm, 3mm diameter")
      (libsource (lib "Electronic Devices_LIB") (part "TP_PAD_SMD_SMALL"))
    )
    (comp (ref "TP12")
      (value "NO COMPONENT")
      (footprint "TP_PAD_0.5MM_SMD_ROUND")
      (description "Test Point, SMD pad, round, 1.5mm, 1.6mm, 3mm diameter")
      (libsource (lib "Electronic Devices_LIB") (part "TP_PAD_SMD_SMALL"))
    )
    (comp (ref "TP13")
      (value "NO COMPONENT")
      (footprint "TP_PAD_0.5MM_SMD_ROUND")
      (description "Test Point, SMD pad, round, 1.5mm, 1.6mm, 3mm diameter")
      (libsource (lib "Electronic Devices_LIB") (part "TP_PAD_SMD_SMALL"))
    )
    (comp (ref "TP14")
      (value "NO COMPONENT")
      (footprint "TP_PAD_0.5MM_SMD_ROUND")
      (description "Test Point, SMD pad, round, 1.5mm, 1.6mm, 3mm diameter")
      (libsource (lib "Electronic Devices_LIB") (part "TP_PAD_SMD_SMALL"))
    )
    (comp (ref "TP15")
      (value "NO COMPONENT")
      (footprint "TP_PAD_0.5MM_SMD_ROUND")
      (description "Test Point, SMD pad, round, 1.5mm, 1.6mm, 3mm diameter")
      (libsource (lib "Electronic Devices_LIB") (part "TP_PAD_SMD_SMALL"))
    )
    (comp (ref "TP16")
      (value "NO COMPONENT")
      (footprint "TP_PAD_0.5MM_SMD_ROUND")
      (description "Test Point, SMD pad, round, 1.5mm, 1.6mm, 3mm diameter")
      (libsource (lib "Electronic Devices_LIB") (part "TP_PAD_SMD_SMALL"))
    )
    (comp (ref "TP17")
      (value "NO COMPONENT")
      (footprint "TP_PAD_0.5MM_SMD_ROUND")
      (description "Test Point, SMD pad, round, 1.5mm, 1.6mm, 3mm diameter")
      (libsource (lib "Electronic Devices_LIB") (part "TP_PAD_SMD_SMALL"))
    )
    (comp (ref "U2")
      (value "MPF7100BVMA1ES")
      (footprint "HVQFN48_SOT619-27D_NXP")
      (description "PMIC, i.MX8, 5 buck, 2 LDO RoHS Compliant: Yes")
      (fields (field (name "MANUFACTURER") "NXP Semiconductors"))
      (libsource (lib "Electronic Devices_LIB") (part "IC_PMIC_IMX8_MPF7100BVMA1ES"))
    )
  )
  (nets
    (net (code "3") (name "/PMIC_FSOB") (class "Default")
      (node (ref "R20") (pin "2") (pinfunction "2_2") (pintype "passive"))
      (node (ref "U2") (pin "36") (pinfunction "FSOB_36") (pintype "passive"))
    )
    (net (code "4") (name "/PMIC_I2C_SCL") (class "Default")
      (node (ref "U2") (pin "11") (pinfunction "SCL_11") (pintype "passive"))
    )
    (net (code "5") (name "/PMIC_I2C_SDA") (class "Default")
      (node (ref "U2") (pin "10") (pinfunction "SDA_10") (pintype "passive"))
    )
    (net (code "6") (name "/PMIC_INT_B") (class "Default")
      (node (ref "R18") (pin "1") (pinfunction "1_1") (pintype "passive"))
    )
    (net (code "7") (name "/PMIC_LDO2_EN") (class "Default")
      (node (ref "R10") (pin "1") (pinfunction "1_1") (pintype "passive"))
      (node (ref "R12") (pin "1") (pinfunction "1_1") (pintype "passive"))
      (node (ref "R14") (pin "2") (pinfunction "2_2") (pintype "passive"))
    )
    (net (code "8") (name "/PMIC_ON_REQ") (class "Default")
      (node (ref "R17") (pin "1") (pinfunction "1_1") (pintype "passive"))
    )
    (net (code "9") (name "/PMIC_PG") (class "Default")
      (node (ref "R23") (pin "1") (pinfunction "1_1") (pintype "passive"))
      (node (ref "TP13") (pin "1") (pinfunction "1_1") (pintype "passive"))
      (node (ref "U2") (pin "38") (pinfunction "PGOOD_38") (pintype "passive"))
    )
    (net (code "10") (name "/PMIC_RESETBMCU") (class "Default")
      (node (ref "R24") (pin "2") (pinfunction "2_2") (pintype "passive"))
      (node (ref "R26") (pin "2") (pinfunction "2_2") (pintype "passive"))
    )
    (net (code "11") (name "/PMIC_STBY") (class "Default")
      (node (ref "R15") (pin "1") (pinfunction "1_1") (pintype "passive"))
    )
    (net (code "12") (name "/PMIC_WDOG_IN") (class "Default")
      (node (ref "R19") (pin "1") (pinfunction "1_1") (pintype "passive"))
    )
    (net (code "13") (name "/SD1_VSELECT") (class "Default")
      (node (ref "R11") (pin "1") (pinfunction "1_1") (pintype "passive"))
      (node (ref "R13") (pin "2") (pinfunction "2_2") (pintype "passive"))
      (node (ref "R9") (pin "1") (pinfunction "1_1") (pintype "passive"))
    )
    (net (code "14") (name "/SW1FB") (class "Default")
      (node (ref "R4") (pin "1") (pinfunction "1_1") (pintype "passive"))
      (node (ref "U2") (pin "31") (pinfunction "SW1FB_31") (pintype "passive"))
    )
    (net (code "15") (name "/SW1LX") (class "Default")
      (node (ref "L1") (pin "1") (pinfunction "1_1") (pintype "passive"))
      (node (ref "U2") (pin "40") (pinfunction "SW1LX_40") (pintype "passive"))
    )
    (net (code "16") (name "/SW2FB") (class "Default")
      (node (ref "R5") (pin "1") (pinfunction "1_1") (pintype "passive"))
      (node (ref "U2") (pin "30") (pinfunction "SW2FB_30") (pintype "passive"))
    )
    (net (code "17") (name "/SW2LX") (class "Default")
      (node (ref "L2") (pin "1") (pinfunction "1_1") (pintype "passive"))
      (node (ref "U2") (pin "41") (pinfunction "SW2LX_41") (pintype "passive"))
    )
    (net (code "18") (name "/SW3FB") (class "Default")
      (node (ref "R6") (pin "1") (pinfunction "1_1") (pintype "passive"))
      (node (ref "U2") (pin "7") (pinfunction "SW3FB_7") (pintype "passive"))
    )
    (net (code "19") (name "/SW3LX") (class "Default")
      (node (ref "L3") (pin "1") (pinfunction "1_1") (pintype "passive"))
      (node (ref "U2") (pin "44") (pinfunction "SW3LX_44") (pintype "passive"))
    )
    (net (code "20") (name "/SW4FB") (class "Default")
      (node (ref "R7") (pin "1") (pinfunction "1_1") (pintype "passive"))
      (node (ref "U2") (pin "6") (pinfunction "SW4FB_6") (pintype "passive"))
    )
    (net (code "21") (name "/SW4LX") (class "Default")
      (node (ref "L4") (pin "1") (pinfunction "1_1") (pintype "passive"))
      (node (ref "U2") (pin "45") (pinfunction "SW4LX_45") (pintype "passive"))
    )
    (net (code "22") (name "/SW5FB") (class "Default")
      (node (ref "R8") (pin "1") (pinfunction "1_1") (pintype "passive"))
      (node (ref "U2") (pin "12") (pinfunction "SW5FB_12") (pintype "passive"))
    )
    (net (code "23") (name "/SW5LX") (class "Default")
      (node (ref "L5") (pin "1") (pinfunction "1_1") (pintype "passive"))
      (node (ref "U2") (pin "16") (pinfunction "SW5LX_16") (pintype "passive"))
    )
    (net (code "26") (name "3V3_PMIC") (class "Default")
      (node (ref "C39") (pin "2") (pinfunction "2_2") (pintype "passive"))
      (node (ref "C40") (pin "2") (pinfunction "2_2") (pintype "passive"))
      (node (ref "C41") (pin "2") (pinfunction "2_2") (pintype "passive"))
      (node (ref "C42") (pin "2") (pinfunction "2_2") (pintype "passive"))
      (node (ref "C43") (pin "2") (pinfunction "2_2") (pintype "passive"))
      (node (ref "C44") (pin "2") (pinfunction "2_2") (pintype "passive"))
      (node (ref "C46") (pin "2") (pinfunction "2_2") (pintype "passive"))
      (node (ref "U2") (pin "15") (pinfunction "SW5IN_15") (pintype "passive"))
      (node (ref "U2") (pin "20") (pinfunction "LDO1IN_20") (pintype "passive"))
      (node (ref "U2") (pin "27") (pinfunction "VIN_27") (pintype "passive"))
      (node (ref "U2") (pin "39") (pinfunction "SW1IN_39") (pintype "passive"))
      (node (ref "U2") (pin "42") (pinfunction "SW2IN_42") (pintype "passive"))
      (node (ref "U2") (pin "43") (pinfunction "SW3IN_43") (pintype "passive"))
      (node (ref "U2") (pin "46") (pinfunction "SW4IN_46") (pintype "passive"))
    )
    (net (code "27") (name "5V0_PS") (class "Default")
      (node (ref "C45") (pin "2") (pinfunction "2_2") (pintype "passive"))
      (node (ref "U2") (pin "19") (pinfunction "LDO2IN_19") (pintype "passive"))
    )
    (net (code "28") (name "GND") (class "Default")
      (node (ref "C39") (pin "1") (pinfunction "1_1") (pintype "passive"))
      (node (ref "C40") (pin "1") (pinfunction "1_1") (pintype "passive"))
      (node (ref "C41") (pin "1") (pinfunction "1_1") (pintype "passive"))
      (node (ref "C42") (pin "1") (pinfunction "1_1") (pintype "passive"))
      (node (ref "C43") (pin "1") (pinfunction "1_1") (pintype "passive"))
      (node (ref "C44") (pin "1") (pinfunction "1_1") (pintype "passive"))
      (node (ref "C45") (pin "1") (pinfunction "1_1") (pintype "passive"))
      (node (ref "C46") (pin "1") (pinfunction "1_1") (pintype "passive"))
      (node (ref "C47") (pin "1") (pinfunction "1_1") (pintype "passive"))
      (node (ref "C48") (pin "1") (pinfunction "1_1") (pintype "passive"))
      (node (ref "C49") (pin "1") (pinfunction "1_1") (pintype "passive"))
      (node (ref "C50") (pin "1") (pinfunction "1_1") (pintype "passive"))
      (node (ref "C51") (pin "1") (pinfunction "1_1") (pintype "passive"))
      (node (ref "C52") (pin "1") (pinfunction "1_1") (pintype "passive"))
      (node (ref "C53") (pin "1") (pinfunction "1_1") (pintype "passive"))
      (node (ref "C54") (pin "1") (pinfunction "1_1") (pintype "passive"))
      (node (ref "C55") (pin "1") (pinfunction "1_1") (pintype "passive"))
      (node (ref "C56") (pin "1") (pinfunction "1_1") (pintype "passive"))
      (node (ref "C57") (pin "1") (pinfunction "1_1") (pintype "passive"))
      (node (ref "C58") (pin "1") (pinfunction "1_1") (pintype "passive"))
      (node (ref "C59") (pin "1") (pinfunction "1_1") (pintype "passive"))
      (node (ref "C60") (pin "1") (pinfunction "1_1") (pintype "passive"))
      (node (ref "C61") (pin "1") (pinfunction "1_1") (pintype "passive"))
      (node (ref "C62") (pin "1") (pinfunction "1_1") (pintype "passive"))
      (node (ref "C63") (pin "1") (pinfunction "1_1") (pintype "passive"))
      (node (ref "C64") (pin "1") (pinfunction "1_1") (pintype "passive"))
      (node (ref "C65") (pin "1") (pinfunction "1_1") (pintype "passive"))
      (node (ref "C66") (pin "1") (pinfunction "1_1") (pintype "passive"))
      (node (ref "C67") (pin "1") (pinfunction "1_1") (pintype "passive"))
      (node (ref "C68") (pin "1") (pinfunction "1_1") (pintype "passive"))
      (node (ref "C69") (pin "1") (pinfunction "1_1") (pintype "passive"))
      (node (ref "C70") (pin "1") (pinfunction "1_1") (pintype "passive"))
      (node (ref "C71") (pin "1") (pinfunction "1_1") (pintype "passive"))
      (node (ref "C72") (pin "1") (pinfunction "1_1") (pintype "passive"))
      (node (ref "C73") (pin "1") (pinfunction "1_1") (pintype "passive"))
      (node (ref "R13") (pin "1") (pinfunction "1_1") (pintype "passive"))
      (node (ref "R14") (pin "1") (pinfunction "1_1") (pintype "passive"))
      (node (ref "R27") (pin "1") (pinfunction "1_1") (pintype "passive"))
      (node (ref "R28") (pin "1") (pinfunction "1_1") (pintype "passive"))
      (node (ref "R29") (pin "1") (pinfunction "1_1") (pintype "passive"))
      (node (ref "R30") (pin "1") (pinfunction "1_1") (pintype "passive"))
      (node (ref "U2") (pin "26") (pinfunction "AGND_26") (pintype "passive"))
      (node (ref "U2") (pin "29") (pinfunction "DGND_29") (pintype "passive"))
      (node (ref "U2") (pin "49") (pinfunction "EPAD_49") (pintype "passive"))
    )
    (net (code "29") (name "Net-(U2-AMUX)") (class "Default")
      (node (ref "TP15") (pin "1") (pinfunction "1_1") (pintype "passive"))
      (node (ref "U2") (pin "25") (pinfunction "AMUX_25") (pintype "passive"))
    )
    (net (code "30") (name "Net-(U2-EWARN)") (class "Default")
      (node (ref "R27") (pin "2") (pinfunction "2_2") (pintype "passive"))
      (node (ref "TP17") (pin "1") (pinfunction "1_1") (pintype "passive"))
      (node (ref "U2") (pin "3") (pinfunction "EWARN_3") (pintype "passive"))
    )
    (net (code "31") (name "Net-(U2-INTB)") (class "Default")
      (node (ref "R18") (pin "2") (pinfunction "2_2") (pintype "passive"))
      (node (ref "U2") (pin "37") (pinfunction "INTB_37") (pintype "passive"))
    )
    (net (code "32") (name "Net-(U2-LDO2EN)") (class "Default")
      (node (ref "R12") (pin "2") (pinfunction "2_2") (pintype "passive"))
      (node (ref "U2") (pin "4") (pinfunction "LDO2EN_4") (pintype "passive"))
    )
    (net (code "33") (name "Net-(U2-PWRON)") (class "Default")
      (node (ref "R17") (pin "2") (pinfunction "2_2") (pintype "passive"))
      (node (ref "U2") (pin "34") (pinfunction "PWRON_34") (pintype "passive"))
    )
    (net (code "34") (name "Net-(U2-RESETBMCU)") (class "Default")
      (node (ref "R26") (pin "1") (pinfunction "1_1") (pintype "passive"))
      (node (ref "U2") (pin "35") (pinfunction "RESETBMCU_35") (pintype "passive"))
    )
    (net (code "35") (name "Net-(U2-STANDBY)") (class "Default")
      (node (ref "R15") (pin "2") (pinfunction "2_2") (pintype "passive"))
      (node (ref "U2") (pin "33") (pinfunction "STANDBY_33") (pintype "passive"))
    )
    (net (code "36") (name "Net-(U2-SYNCIN)") (class "Default")
      (node (ref "R30") (pin "2") (pinfunction "2_2") (pintype "passive"))
      (node (ref "TP16") (pin "1") (pinfunction "1_1") (pintype "passive"))
      (node (ref "U2") (pin "5") (pinfunction "SYNCIN_5") (pintype "passive"))
    )
    (net (code "37") (name "Net-(U2-SYNCOUT)") (class "Default")
      (node (ref "TP14") (pin "1") (pinfunction "1_1") (pintype "passive"))
      (node (ref "U2") (pin "2") (pinfunction "SYNCOUT_2") (pintype "passive"))
    )
    (net (code "38") (name "Net-(U2-TBBEN)") (class "Default")
      (node (ref "R22") (pin "1") (pinfunction "1_1") (pintype "passive"))
      (node (ref "R29") (pin "2") (pinfunction "2_2") (pintype "passive"))
      (node (ref "U2") (pin "32") (pinfunction "TBBEN_32") (pintype "passive"))
    )
    (net (code "39") (name "Net-(U2-VDDOTP)") (class "Default")
      (node (ref "R21") (pin "1") (pinfunction "1_1") (pintype "passive"))
      (node (ref "R28") (pin "2") (pinfunction "2_2") (pintype "passive"))
      (node (ref "U2") (pin "8") (pinfunction "VDDOTP_8") (pintype "passive"))
    )
    (net (code "40") (name "Net-(U2-VSELECT)") (class "Default")
      (node (ref "R11") (pin "2") (pinfunction "2_2") (pintype "passive"))
      (node (ref "U2") (pin "48") (pinfunction "VSELECT_48") (pintype "passive"))
    )
    (net (code "41") (name "Net-(U2-VSNVS2)") (class "Default")
      (node (ref "R16") (pin "1") (pinfunction "1_1") (pintype "passive"))
      (node (ref "TP9") (pin "1") (pinfunction "1_1") (pintype "passive"))
      (node (ref "U2") (pin "22") (pinfunction "VSNVS2_22") (pintype "passive"))
    )
    (net (code "42") (name "Net-(U2-WDI)") (class "Default")
      (node (ref "R19") (pin "2") (pinfunction "2_2") (pintype "passive"))
      (node (ref "U2") (pin "1") (pinfunction "WDI_1") (pintype "passive"))
    )
    (net (code "43") (name "Net-(U2-XFAILB)") (class "Default")
      (node (ref "R25") (pin "1") (pinfunction "1_1") (pintype "passive"))
      (node (ref "U2") (pin "17") (pinfunction "XFAILB_17") (pintype "passive"))
    )
    (net (code "44") (name "PMIC_VDD_1V8") (class "Default")
      (node (ref "C47") (pin "2") (pinfunction "2_2") (pintype "passive"))
      (node (ref "C70") (pin "2") (pinfunction "2_2") (pintype "passive"))
      (node (ref "C71") (pin "2") (pinfunction "2_2") (pintype "passive"))
      (node (ref "C72") (pin "2") (pinfunction "2_2") (pintype "passive"))
      (node (ref "C73") (pin "2") (pinfunction "2_2") (pintype "passive"))
      (node (ref "L5") (pin "2") (pinfunction "2_2") (pintype "passive"))
      (node (ref "R10") (pin "2") (pinfunction "2_2") (pintype "passive"))
      (node (ref "R20") (pin "1") (pinfunction "1_1") (pintype "passive"))
      (node (ref "R23") (pin "2") (pinfunction "2_2") (pintype "passive"))
      (node (ref "R24") (pin "1") (pinfunction "1_1") (pintype "passive"))
      (node (ref "R8") (pin "2") (pinfunction "2_2") (pintype "passive"))
      (node (ref "R9") (pin "2") (pinfunction "2_2") (pintype "passive"))
      (node (ref "TP5") (pin "1") (pinfunction "1_1") (pintype "passive"))
      (node (ref "U2") (pin "9") (pinfunction "VDDIO_9") (pintype "passive"))
    )
    (net (code "45") (name "PMIC_VDD_ANA") (class "Default")
      (node (ref "C48") (pin "2") (pinfunction "2_2") (pintype "passive"))
      (node (ref "TP6") (pin "1") (pinfunction "1_1") (pintype "passive"))
      (node (ref "U2") (pin "21") (pinfunction "LDO1OUT_21") (pintype "passive"))
    )
    (net (code "46") (name "PMIC_VDD_DDRIO") (class "Default")
      (node (ref "C66") (pin "2") (pinfunction "2_2") (pintype "passive"))
      (node (ref "C67") (pin "2") (pinfunction "2_2") (pintype "passive"))
      (node (ref "C68") (pin "2") (pinfunction "2_2") (pintype "passive"))
      (node (ref "C69") (pin "2") (pinfunction "2_2") (pintype "passive"))
      (node (ref "L4") (pin "2") (pinfunction "2_2") (pintype "passive"))
      (node (ref "R7") (pin "2") (pinfunction "2_2") (pintype "passive"))
      (node (ref "TP4") (pin "1") (pinfunction "1_1") (pintype "passive"))
    )
    (net (code "47") (name "PMIC_VDD_MAIN") (class "Default")
      (node (ref "C54") (pin "2") (pinfunction "2_2") (pintype "passive"))
      (node (ref "C55") (pin "2") (pinfunction "2_2") (pintype "passive"))
      (node (ref "C56") (pin "2") (pinfunction "2_2") (pintype "passive"))
      (node (ref "C57") (pin "2") (pinfunction "2_2") (pintype "passive"))
      (node (ref "L1") (pin "2") (pinfunction "2_2") (pintype "passive"))
      (node (ref "R4") (pin "2") (pinfunction "2_2") (pintype "passive"))
      (node (ref "TP1") (pin "1") (pinfunction "1_1") (pintype "passive"))
    )
    (net (code "48") (name "PMIC_VDD_MEMC") (class "Default")
      (node (ref "C58") (pin "2") (pinfunction "2_2") (pintype "passive"))
      (node (ref "C59") (pin "2") (pinfunction "2_2") (pintype "passive"))
      (node (ref "C60") (pin "2") (pinfunction "2_2") (pintype "passive"))
      (node (ref "C61") (pin "2") (pinfunction "2_2") (pintype "passive"))
      (node (ref "L2") (pin "2") (pinfunction "2_2") (pintype "passive"))
      (node (ref "R5") (pin "2") (pinfunction "2_2") (pintype "passive"))
      (node (ref "TP2") (pin "1") (pinfunction "1_1") (pintype "passive"))
    )
    (net (code "49") (name "PMIC_VDD_SD") (class "Default")
      (node (ref "C49") (pin "2") (pinfunction "2_2") (pintype "passive"))
      (node (ref "TP7") (pin "1") (pinfunction "1_1") (pintype "passive"))
      (node (ref "U2") (pin "18") (pinfunction "LDO2OUT_18") (pintype "passive"))
    )
    (net (code "50") (name "PMIC_VDD_SNVS1") (class "Default")
      (node (ref "C51") (pin "2") (pinfunction "2_2") (pintype "passive"))
      (node (ref "TP8") (pin "1") (pinfunction "1_1") (pintype "passive"))
      (node (ref "U2") (pin "23") (pinfunction "VSNVS1_23") (pintype "passive"))
    )
    (net (code "51") (name "PMIC_VDD_SNVS2") (class "Default")
      (node (ref "C50") (pin "2") (pinfunction "2_2") (pintype "passive"))
      (node (ref "R16") (pin "2") (pinfunction "2_2") (pintype "passive"))
      (node (ref "TP10") (pin "1") (pinfunction "1_1") (pintype "passive"))
    )
    (net (code "52") (name "PMIC_VDD_V2X_VTT") (class "Default")
      (node (ref "C62") (pin "2") (pinfunction "2_2") (pintype "passive"))
      (node (ref "C63") (pin "2") (pinfunction "2_2") (pintype "passive"))
      (node (ref "C64") (pin "2") (pinfunction "2_2") (pintype "passive"))
      (node (ref "C65") (pin "2") (pinfunction "2_2") (pintype "passive"))
      (node (ref "L3") (pin "2") (pinfunction "2_2") (pintype "passive"))
      (node (ref "R6") (pin "2") (pinfunction "2_2") (pintype "passive"))
      (node (ref "TP3") (pin "1") (pinfunction "1_1") (pintype "passive"))
    )
    (net (code "53") (name "V1P5A_1V5") (class "Default")
      (node (ref "C52") (pin "2") (pinfunction "2_2") (pintype "passive"))
      (node (ref "R25") (pin "2") (pinfunction "2_2") (pintype "passive"))
      (node (ref "TP11") (pin "1") (pinfunction "1_1") (pintype "passive"))
      (node (ref "U2") (pin "24") (pinfunction "V1P5A_24") (pintype "passive"))
    )
    (net (code "54") (name "V1P5D_1V5") (class "Default")
      (node (ref "C53") (pin "2") (pinfunction "2_2") (pintype "passive"))
      (node (ref "R21") (pin "2") (pinfunction "2_2") (pintype "passive"))
      (node (ref "R22") (pin "2") (pinfunction "2_2") (pintype "passive"))
      (node (ref "TP12") (pin "1") (pinfunction "1_1") (pintype "passive"))
      (node (ref "U2") (pin "28") (pinfunction "V1P5D_28") (pintype "passive"))
    )
    (net (code "55") (name "unconnected-(U2-NC-Pad47)") (class "Default")
      (node (ref "U2") (pin "47") (pinfunction "NC_47") (pintype "passive+no_connect"))
    )
    (net (code "56") (name "unconnected-(U2-NC1-Pad14)") (class "Default")
      (node (ref "U2") (pin "14") (pinfunction "NC1_14") (pintype "passive+no_connect"))
    )
    (net (code "57") (name "unconnected-(U2-XINTB-Pad13)") (class "Default")
      (node (ref "U2") (pin "13") (pinfunction "XINTB_13") (pintype "passive+no_connect"))
    )
  )
)
